# 07_-_PCIE_MINI.net
KiCad netlist of a schematic drawn in Altium Designer
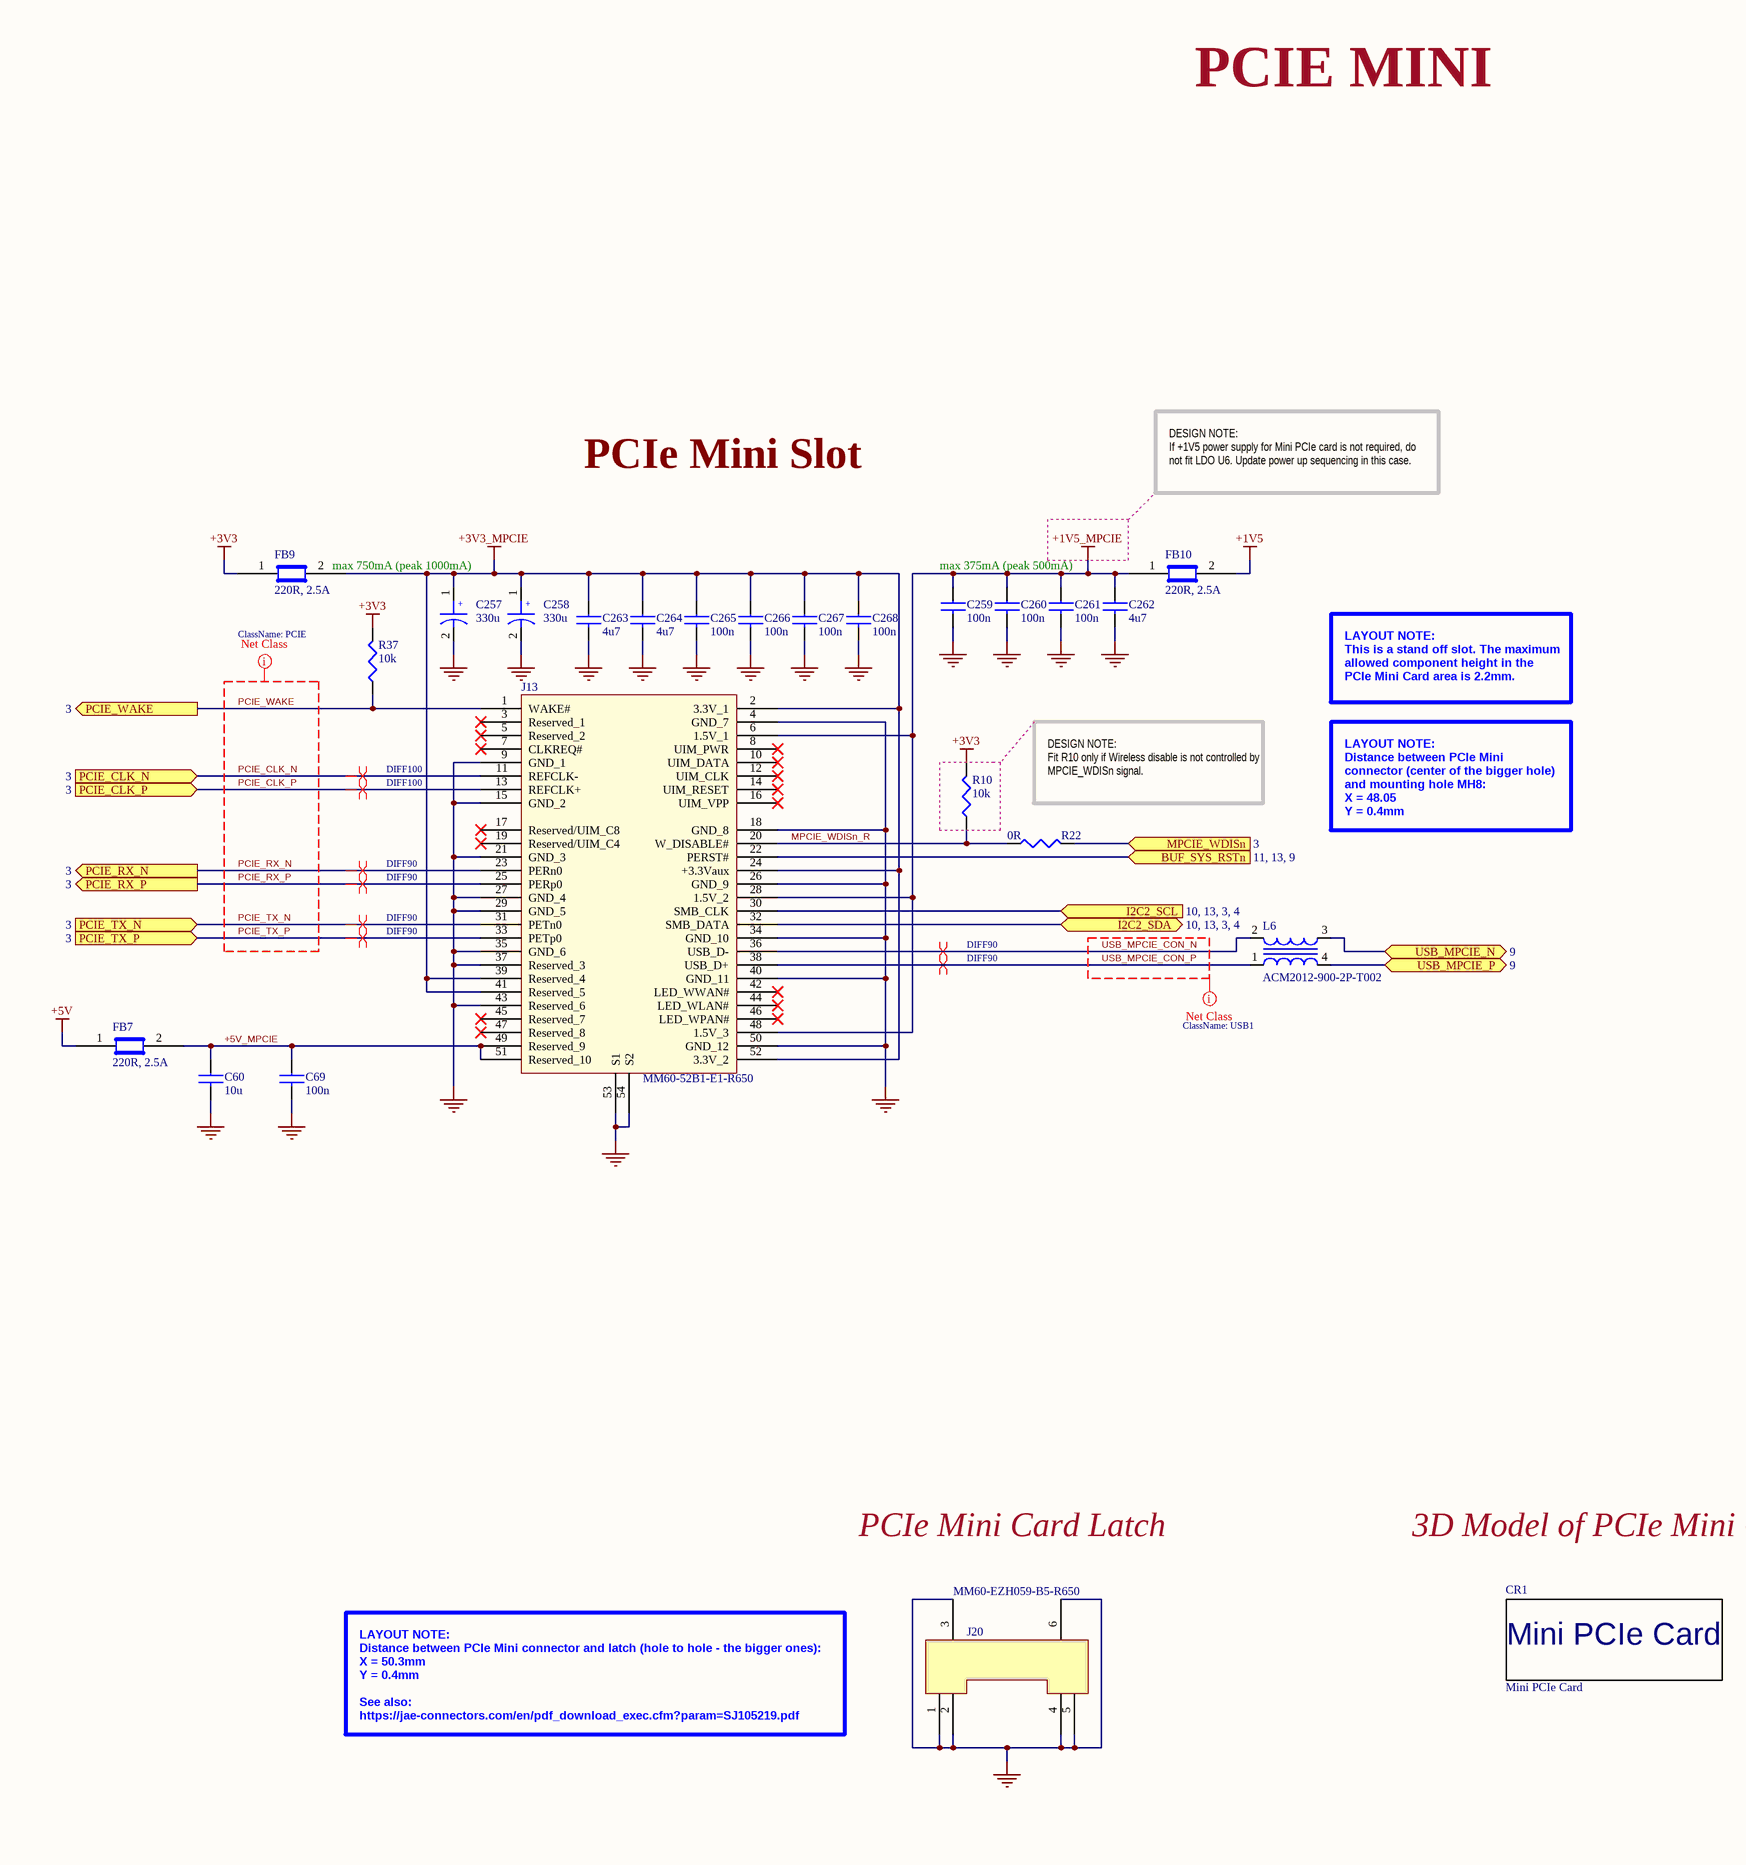
[diagram p0: [07] - PCIE MINI.SchDoc, left]
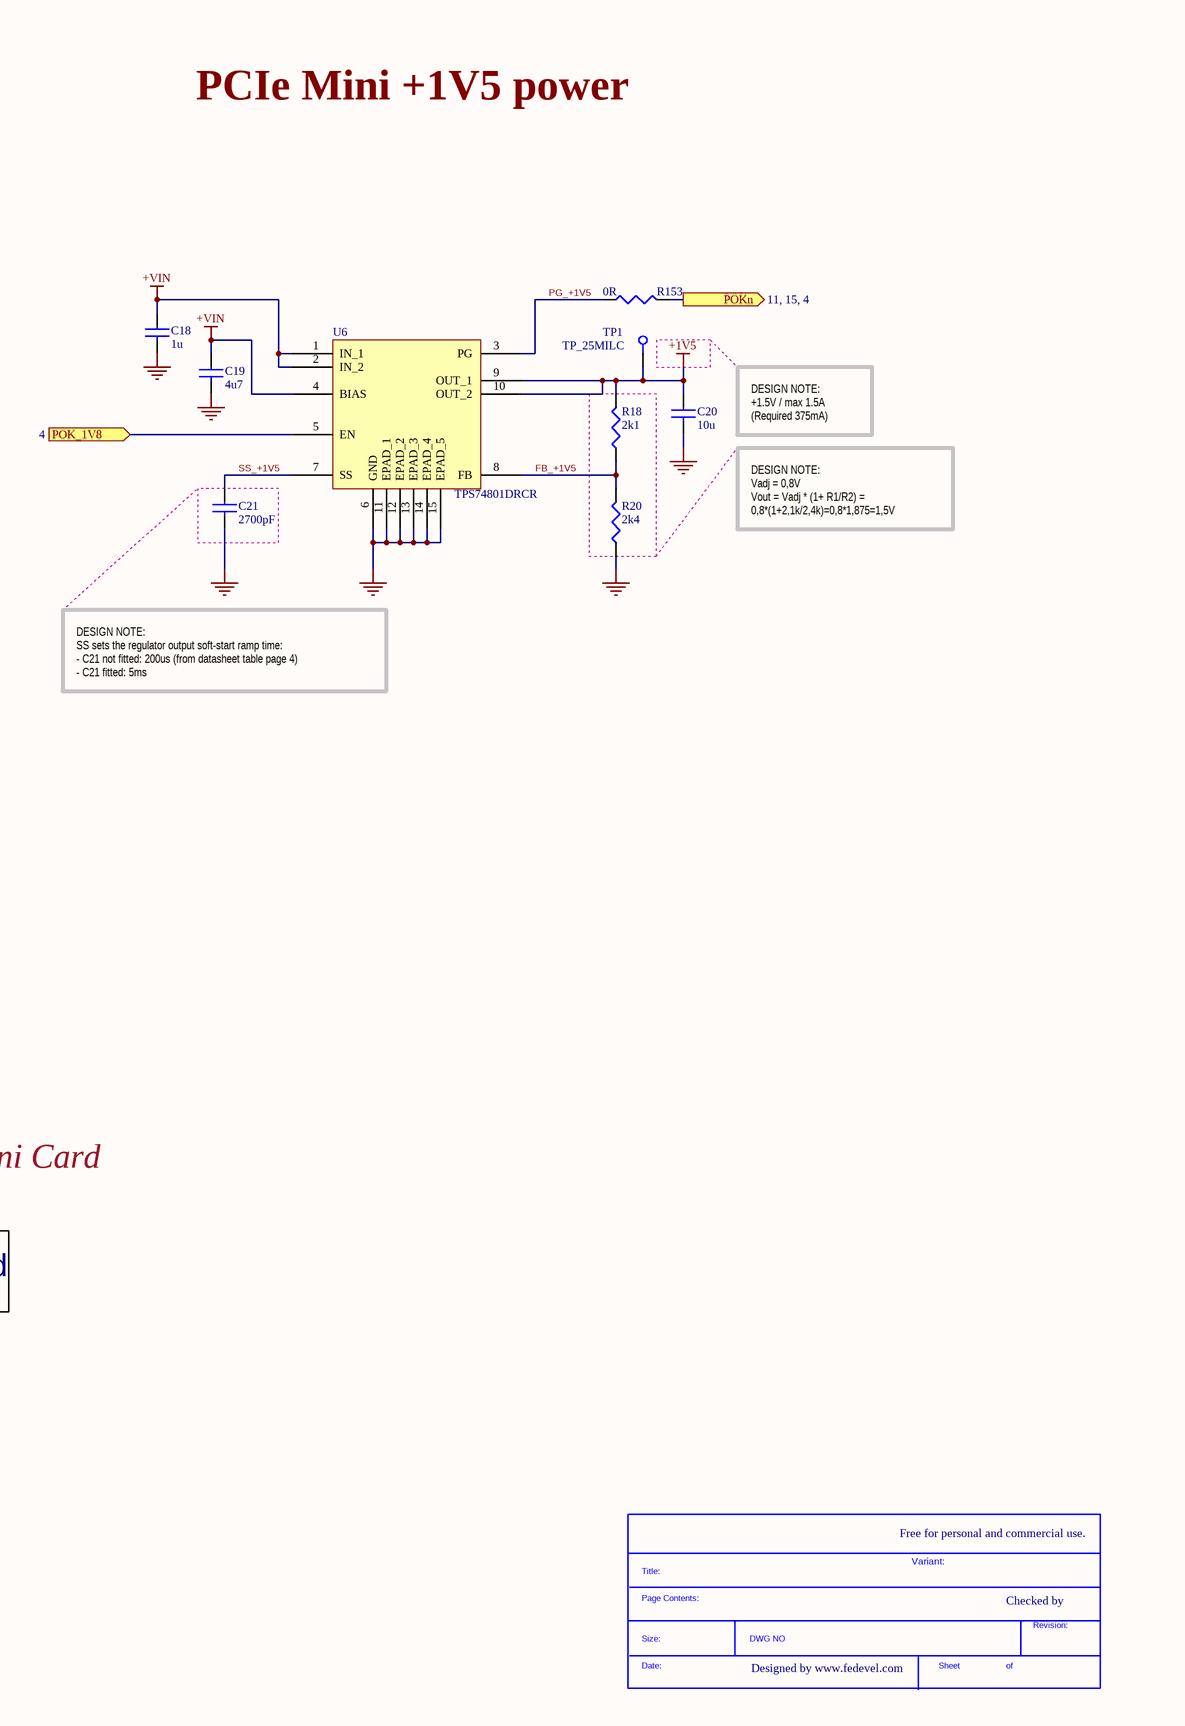
[diagram p1: [07] - PCIE MINI.SchDoc, right]

(export (version "E")
  (design (tool "Eeschema 10.0.6"))
  (components
    (comp (ref "C18")
      (value "1u")
      (footprint "C0402")
      (description "CAP CER 1.0UF 16V X5R 0402")
      (fields
        (field (name "MANUFACTURER") "TDK Corporation")
        (field (name "MANUFACTURER PART NUMBER") "C1005X5R1C105K")
      )
      (libsource (lib "Integrated_Library_FEDEVEL_APR_2015") (part "C1005X5R1C105K"))
    )
    (comp (ref "C19")
      (value "4u7")
      (footprint "C0402")
      (description "CAP CER 4.7UF 10V 20% X5R 0402")
      (fields
        (field (name "MANUFACTURER") "TDK Corporation")
        (field (name "MANUFACTURER PART NUMBER") "C1005X5R1A475M")
      )
      (libsource (lib "Integrated_Library_FEDEVEL_APR_2015") (part "C1005X5R1A475M"))
    )
    (comp (ref "C20")
      (value "10u")
      (footprint "C0603")
      (description "CAP CER 10UF 6.3V X5R 20% 0603")
      (fields
        (field (name "MANUFACTURER") "TDK Corporation")
        (field (name "MANUFACTURER PART NUMBER") "C1608X5R0J106M")
      )
      (libsource (lib "Integrated_Library_FEDEVEL_APR_2015") (part "C1608X5R0J106M"))
    )
    (comp (ref "C21")
      (value "2700pF")
      (footprint "C0402")
      (description "CAP CER 2700PF 50V 10% X7R 0402")
      (fields
        (field (name "MANUFACTURER") "Murata Electronics North America")
        (field (name "MANUFACTURER PART NUMBER") "GRM155R71H272KA01D")
      )
      (libsource (lib "Integrated_Library_FEDEVEL_APR_2015") (part "GRM155R71H272KA01D"))
    )
    (comp (ref "C60")
      (value "10u")
      (footprint "C0603")
      (description "CAP CER 10UF 6.3V X5R 20% 0603")
      (fields
        (field (name "MANUFACTURER") "TDK Corporation")
        (field (name "MANUFACTURER PART NUMBER") "C1608X5R0J106M")
      )
      (libsource (lib "Integrated_Library_FEDEVEL_APR_2015") (part "C1608X5R0J106M"))
    )
    (comp (ref "C69")
      (value "100n")
      (footprint "C0402")
      (description "CAP CER .10UF 50V X5R 10% 0402")
      (fields
        (field (name "MANUFACTURER") "TDK Corporation")
        (field (name "MANUFACTURER PART NUMBER") "C1005X5R1H104K")
      )
      (libsource (lib "Integrated_Library_FEDEVEL_APR_2015") (part "C1005X5R1H104K"))
    )
    (comp (ref "C257")
      (value "330u")
      (footprint "C2917")
      (description "CAP TANT 330UF 6.3V 20% 2917")
      (fields
        (field (name "MANUFACTURER") "Kemet")
        (field (name "MANUFACTURER PART NUMBER") "T520D337M006ATE045")
        (field (name ".CREATOR") "MM")
      )
      (libsource (lib "Integrated_Library_FEDEVEL_APR_2015") (part "T520D337M006ATE045"))
    )
    (comp (ref "C258")
      (value "330u")
      (footprint "C2917")
      (description "CAP TANT 330UF 6.3V 20% 2917")
      (fields
        (field (name "MANUFACTURER") "Kemet")
        (field (name "MANUFACTURER PART NUMBER") "T520D337M006ATE045")
        (field (name ".CREATOR") "MM")
      )
      (libsource (lib "Integrated_Library_FEDEVEL_APR_2015") (part "T520D337M006ATE045"))
    )
    (comp (ref "C259")
      (value "100n")
      (footprint "C0402")
      (description "CAP CER .10UF 50V X5R 10% 0402")
      (fields
        (field (name "MANUFACTURER") "TDK Corporation")
        (field (name "MANUFACTURER PART NUMBER") "C1005X5R1H104K")
      )
      (libsource (lib "Integrated_Library_FEDEVEL_APR_2015") (part "C1005X5R1H104K"))
    )
    (comp (ref "C260")
      (value "100n")
      (footprint "C0402")
      (description "CAP CER .10UF 50V X5R 10% 0402")
      (fields
        (field (name "MANUFACTURER") "TDK Corporation")
        (field (name "MANUFACTURER PART NUMBER") "C1005X5R1H104K")
      )
      (libsource (lib "Integrated_Library_FEDEVEL_APR_2015") (part "C1005X5R1H104K"))
    )
    (comp (ref "C261")
      (value "100n")
      (footprint "C0402")
      (description "CAP CER .10UF 50V X5R 10% 0402")
      (fields
        (field (name "MANUFACTURER") "TDK Corporation")
        (field (name "MANUFACTURER PART NUMBER") "C1005X5R1H104K")
      )
      (libsource (lib "Integrated_Library_FEDEVEL_APR_2015") (part "C1005X5R1H104K"))
    )
    (comp (ref "C262")
      (value "4u7")
      (footprint "C0402")
      (description "CAP CER 4.7UF 10V 20% X5R 0402")
      (fields
        (field (name "MANUFACTURER") "TDK Corporation")
        (field (name "MANUFACTURER PART NUMBER") "C1005X5R1A475M")
      )
      (libsource (lib "Integrated_Library_FEDEVEL_APR_2015") (part "C1005X5R1A475M"))
    )
    (comp (ref "C263")
      (value "4u7")
      (footprint "C0402")
      (description "CAP CER 4.7UF 10V 20% X5R 0402")
      (fields
        (field (name "MANUFACTURER") "TDK Corporation")
        (field (name "MANUFACTURER PART NUMBER") "C1005X5R1A475M")
      )
      (libsource (lib "Integrated_Library_FEDEVEL_APR_2015") (part "C1005X5R1A475M"))
    )
    (comp (ref "C264")
      (value "4u7")
      (footprint "C0402")
      (description "CAP CER 4.7UF 10V 20% X5R 0402")
      (fields
        (field (name "MANUFACTURER") "TDK Corporation")
        (field (name "MANUFACTURER PART NUMBER") "C1005X5R1A475M")
      )
      (libsource (lib "Integrated_Library_FEDEVEL_APR_2015") (part "C1005X5R1A475M"))
    )
    (comp (ref "C265")
      (value "100n")
      (footprint "C0402")
      (description "CAP CER .10UF 50V X5R 10% 0402")
      (fields
        (field (name "MANUFACTURER") "TDK Corporation")
        (field (name "MANUFACTURER PART NUMBER") "C1005X5R1H104K")
      )
      (libsource (lib "Integrated_Library_FEDEVEL_APR_2015") (part "C1005X5R1H104K"))
    )
    (comp (ref "C266")
      (value "100n")
      (footprint "C0402")
      (description "CAP CER .10UF 50V X5R 10% 0402")
      (fields
        (field (name "MANUFACTURER") "TDK Corporation")
        (field (name "MANUFACTURER PART NUMBER") "C1005X5R1H104K")
      )
      (libsource (lib "Integrated_Library_FEDEVEL_APR_2015") (part "C1005X5R1H104K"))
    )
    (comp (ref "C267")
      (value "100n")
      (footprint "C0402")
      (description "CAP CER .10UF 50V X5R 10% 0402")
      (fields
        (field (name "MANUFACTURER") "TDK Corporation")
        (field (name "MANUFACTURER PART NUMBER") "C1005X5R1H104K")
      )
      (libsource (lib "Integrated_Library_FEDEVEL_APR_2015") (part "C1005X5R1H104K"))
    )
    (comp (ref "C268")
      (value "100n")
      (footprint "C0402")
      (description "CAP CER .10UF 50V X5R 10% 0402")
      (fields
        (field (name "MANUFACTURER") "TDK Corporation")
        (field (name "MANUFACTURER PART NUMBER") "C1005X5R1H104K")
      )
      (libsource (lib "Integrated_Library_FEDEVEL_APR_2015") (part "C1005X5R1H104K"))
    )
    (comp (ref "CR1")
      (value "Mini PCIe Card")
      (footprint "Mini_PCIe_full card")
      (description "Card MIni PCIe")
      (fields (field (name ".CREATOR") "MM"))
      (libsource (lib "Integrated_Library_FEDEVEL_APR_2015") (part "Card_Mini_PCIe"))
    )
    (comp (ref "FB7")
      (value "220R, 2.5A")
      (footprint "C0603")
      (description "FERRITE CHIP 220 OHM 2500MA 0603")
      (fields
        (field (name "MANUFACTURER") "Murata Electronics North America")
        (field (name "MANUFACTURER PART NUMBER") "BLM18SG221TN1D")
      )
      (libsource (lib "Integrated_Library_FEDEVEL_APR_2015") (part "BLM18SG221TN1D"))
    )
    (comp (ref "FB9")
      (value "220R, 2.5A")
      (footprint "C0603")
      (description "FERRITE CHIP 220 OHM 2500MA 0603")
      (fields
        (field (name "MANUFACTURER") "Murata Electronics North America")
        (field (name "MANUFACTURER PART NUMBER") "BLM18SG221TN1D")
      )
      (libsource (lib "Integrated_Library_FEDEVEL_APR_2015") (part "BLM18SG221TN1D"))
    )
    (comp (ref "FB10")
      (value "220R, 2.5A")
      (footprint "C0603")
      (description "FERRITE CHIP 220 OHM 2500MA 0603")
      (fields
        (field (name "MANUFACTURER") "Murata Electronics North America")
        (field (name "MANUFACTURER PART NUMBER") "BLM18SG221TN1D")
      )
      (libsource (lib "Integrated_Library_FEDEVEL_APR_2015") (part "BLM18SG221TN1D"))
    )
    (comp (ref "J13")
      (value "MM60-52B1-E1-R650")
      (footprint "MINI_PCIE_52PIN_CARD_CON")
      (description "CONN MINI EXPRESS CARD 52POS SMD")
      (fields (field (name "MANUFACTURER") "JAE Electronics") (field (name ".CREATOR") "MM"))
      (libsource (lib "Integrated_Library_FEDEVEL_APR_2015") (part "MM60-52B1-E1-R650"))
    )
    (comp (ref "J20")
      (value "MM60-EZH059-B5-R650")
      (footprint "MINI_PCIE_52PIN_CARD_LATCH")
      (description "CONN MINI EXPRESS CARD LATCH SMD")
      (fields (field (name "MANUFACTURER") "JAE Electronics") (field (name ".CREATOR") "MM"))
      (libsource (lib "Integrated_Library_FEDEVEL_APR_2015") (part "MM60-EZH059-B5-R650"))
    )
    (comp (ref "L6")
      (value "ACM2012-900-2P-T002")
      (footprint "ACM2012")
      (description "CHOKE COMM MODE 90 OHM .4A SMD")
      (fields (field (name "MANUFACTURER") "TDK Corporation") (field (name "TOLERANCE") "±1%"))
      (libsource (lib "Integrated_Library_FEDEVEL_APR_2015") (part "ACM2012-900-2P-T002"))
    )
    (comp (ref "R10")
      (value "10k")
      (footprint "R0402")
      (description "RES 10.0K OHM 1/16W 1% 0402 SMD")
      (fields
        (field (name "MANUFACTURER") "Yageo")
        (field (name "MANUFACTURER PART NUMBER") "RC0402FR-0710KL")
      )
      (libsource (lib "Integrated_Library_FEDEVEL_APR_2015") (part "RC0402FR-0710KL"))
    )
    (comp (ref "R18")
      (value "2k1")
      (footprint "R0402")
      (description "RES 2.10K OHM 1/16W 1% 0402 SMD")
      (fields
        (field (name "MANUFACTURER") "Vishay Dale")
        (field (name "MANUFACTURER PART NUMBER") "CRCW04022K10FKED")
        (field (name ".CREATOR") "MM")
      )
      (libsource (lib "Integrated_Library_FEDEVEL_APR_2015") (part "CRCW04022K10FKED"))
    )
    (comp (ref "R20")
      (value "2k4")
      (footprint "R0402")
      (description "RES 2.40K OHM 1/16W 1% 0402 SMD")
      (fields
        (field (name "MANUFACTURER") "Vishay Dale")
        (field (name "MANUFACTURER PART NUMBER") "CRCW04022K40FKED")
      )
      (libsource (lib "Integrated_Library_FEDEVEL_APR_2015") (part "CRCW04022K40FKED"))
    )
    (comp (ref "R22")
      (value "0R")
      (footprint "R0402")
      (description "RES 0.0 OHM 1/16W 0402 SMD")
      (fields
        (field (name "MANUFACTURER") "Yageo")
        (field (name "MANUFACTURER PART NUMBER") "RC0402JR-070RL")
      )
      (libsource (lib "Integrated_Library_FEDEVEL_APR_2015") (part "RC0402JR-070RL"))
    )
    (comp (ref "R37")
      (value "10k")
      (footprint "R0402")
      (description "RES 10.0K OHM 1/16W 1% 0402 SMD")
      (fields
        (field (name "MANUFACTURER") "Yageo")
        (field (name "MANUFACTURER PART NUMBER") "RC0402FR-0710KL")
      )
      (libsource (lib "Integrated_Library_FEDEVEL_APR_2015") (part "RC0402FR-0710KL"))
    )
    (comp (ref "R153")
      (value "0R")
      (footprint "R0402")
      (description "RES 0.0 OHM 1/16W 0402 SMD")
      (fields
        (field (name "MANUFACTURER") "Yageo")
        (field (name "MANUFACTURER PART NUMBER") "RC0402JR-070RL")
      )
      (libsource (lib "Integrated_Library_FEDEVEL_APR_2015") (part "RC0402JR-070RL"))
    )
    (comp (ref "TP1")
      (value "TP_25MILC")
      (footprint "TP_25C")
      (description "Test Point 25mil")
      (libsource (lib "Integrated_Library_FEDEVEL_APR_2015") (part "TP_25MILC"))
    )
    (comp (ref "U6")
      (value "TPS74801DRCR")
      (footprint "DRC (S-PVSON-N10)")
      (description "IC REG LDO ADJ 1.5A 10SON")
      (fields (field (name "MANUFACTURER") "Texas Instruments") (field (name ".CREATOR") "MM"))
      (libsource (lib "Integrated_Library_FEDEVEL_APR_2015") (part "TPS74801DRCR"))
    )
  )
  (nets
    (net (code "1") (name "+1V5") (class "Default")
      (node (ref "C20") (pin "1") (pinfunction "1_1") (pintype "passive"))
      (node (ref "FB10") (pin "2") (pinfunction "2_2") (pintype "passive"))
      (node (ref "R18") (pin "2") (pinfunction "2_2") (pintype "passive"))
      (node (ref "TP1") (pin "1") (pinfunction "1_1") (pintype "passive"))
      (node (ref "U6") (pin "10") (pinfunction "OUT_2_10") (pintype "passive"))
      (node (ref "U6") (pin "9") (pinfunction "OUT_1_9") (pintype "passive"))
    )
    (net (code "2") (name "+1V5_MPCIE") (class "Default")
      (node (ref "C259") (pin "1") (pinfunction "1_1") (pintype "passive"))
      (node (ref "C260") (pin "1") (pinfunction "1_1") (pintype "passive"))
      (node (ref "C261") (pin "1") (pinfunction "1_1") (pintype "passive"))
      (node (ref "C262") (pin "1") (pinfunction "1_1") (pintype "passive"))
      (node (ref "FB10") (pin "1") (pinfunction "1_1") (pintype "passive"))
      (node (ref "J13") (pin "28") (pinfunction "1.5V_2_28") (pintype "passive"))
      (node (ref "J13") (pin "48") (pinfunction "1.5V_3_48") (pintype "passive"))
      (node (ref "J13") (pin "6") (pinfunction "1.5V_1_6") (pintype "passive"))
    )
    (net (code "3") (name "+3V3") (class "Default")
      (node (ref "FB9") (pin "1") (pinfunction "1_1") (pintype "passive"))
      (node (ref "R10") (pin "2") (pinfunction "2_2") (pintype "passive"))
      (node (ref "R37") (pin "2") (pinfunction "2_2") (pintype "passive"))
    )
    (net (code "4") (name "+3V3_MPCIE") (class "Default")
      (node (ref "C257") (pin "1") (pinfunction "1_1") (pintype "passive"))
      (node (ref "C258") (pin "1") (pinfunction "1_1") (pintype "passive"))
      (node (ref "C263") (pin "1") (pinfunction "1_1") (pintype "passive"))
      (node (ref "C264") (pin "1") (pinfunction "1_1") (pintype "passive"))
      (node (ref "C265") (pin "1") (pinfunction "1_1") (pintype "passive"))
      (node (ref "C266") (pin "1") (pinfunction "1_1") (pintype "passive"))
      (node (ref "C267") (pin "1") (pinfunction "1_1") (pintype "passive"))
      (node (ref "C268") (pin "1") (pinfunction "1_1") (pintype "passive"))
      (node (ref "FB9") (pin "2") (pinfunction "2_2") (pintype "passive"))
      (node (ref "J13") (pin "2") (pinfunction "3.3V_1_2") (pintype "passive"))
      (node (ref "J13") (pin "24") (pinfunction "+3.3Vaux_24") (pintype "passive"))
      (node (ref "J13") (pin "39") (pinfunction "Reserved_4_39") (pintype "passive"))
      (node (ref "J13") (pin "41") (pinfunction "Reserved_5_41") (pintype "passive"))
      (node (ref "J13") (pin "52") (pinfunction "3.3V_2_52") (pintype "passive"))
    )
    (net (code "5") (name "+5V") (class "Default")
      (node (ref "FB7") (pin "1") (pinfunction "1_1") (pintype "passive"))
    )
    (net (code "6") (name "+VIN") (class "Default")
      (node (ref "C18") (pin "1") (pinfunction "1_1") (pintype "passive"))
      (node (ref "C19") (pin "1") (pinfunction "1_1") (pintype "passive"))
      (node (ref "U6") (pin "1") (pinfunction "IN_1_1") (pintype "passive"))
      (node (ref "U6") (pin "2") (pinfunction "IN_2_2") (pintype "passive"))
      (node (ref "U6") (pin "4") (pinfunction "BIAS_4") (pintype "passive"))
    )
    (net (code "7") (name "/+5V_MPCIE") (class "Default")
      (node (ref "C60") (pin "1") (pinfunction "1_1") (pintype "passive"))
      (node (ref "C69") (pin "1") (pinfunction "1_1") (pintype "passive"))
      (node (ref "FB7") (pin "2") (pinfunction "2_2") (pintype "passive"))
      (node (ref "J13") (pin "49") (pinfunction "Reserved_9_49") (pintype "passive"))
      (node (ref "J13") (pin "51") (pinfunction "Reserved_10_51") (pintype "passive"))
    )
    (net (code "8") (name "/BUF_SYS_RSTn") (class "Default")
      (node (ref "J13") (pin "22") (pinfunction "PERST#_22") (pintype "passive"))
    )
    (net (code "9") (name "/FB_+1V5") (class "Default")
      (node (ref "R18") (pin "1") (pinfunction "1_1") (pintype "passive"))
      (node (ref "R20") (pin "2") (pinfunction "2_2") (pintype "passive"))
      (node (ref "U6") (pin "8") (pinfunction "FB_8") (pintype "passive"))
    )
    (net (code "10") (name "/I2C2_SCL") (class "Default")
      (node (ref "J13") (pin "30") (pinfunction "SMB_CLK_30") (pintype "passive"))
    )
    (net (code "11") (name "/I2C2_SDA") (class "Default")
      (node (ref "J13") (pin "32") (pinfunction "SMB_DATA_32") (pintype "passive"))
    )
    (net (code "12") (name "/MPCIE_WDISn") (class "Default")
      (node (ref "R22") (pin "2") (pinfunction "2_2") (pintype "passive"))
    )
    (net (code "13") (name "/MPCIE_WDISn_R") (class "Default")
      (node (ref "J13") (pin "20") (pinfunction "W_DISABLE#_20") (pintype "passive"))
      (node (ref "R10") (pin "1") (pinfunction "1_1") (pintype "passive"))
      (node (ref "R22") (pin "1") (pinfunction "1_1") (pintype "passive"))
    )
    (net (code "14") (name "/PCIE_CLK_N") (class "Default")
      (node (ref "J13") (pin "11") (pinfunction "REFCLK-_11") (pintype "passive"))
    )
    (net (code "15") (name "/PCIE_CLK_P") (class "Default")
      (node (ref "J13") (pin "13") (pinfunction "REFCLK+_13") (pintype "passive"))
    )
    (net (code "16") (name "/PCIE_RX_N") (class "Default")
      (node (ref "J13") (pin "23") (pinfunction "PERn0_23") (pintype "passive"))
    )
    (net (code "17") (name "/PCIE_RX_P") (class "Default")
      (node (ref "J13") (pin "25") (pinfunction "PERp0_25") (pintype "passive"))
    )
    (net (code "18") (name "/PCIE_TX_N") (class "Default")
      (node (ref "J13") (pin "31") (pinfunction "PETn0_31") (pintype "passive"))
    )
    (net (code "19") (name "/PCIE_TX_P") (class "Default")
      (node (ref "J13") (pin "33") (pinfunction "PETp0_33") (pintype "passive"))
    )
    (net (code "20") (name "/PCIE_WAKE") (class "Default")
      (node (ref "J13") (pin "1") (pinfunction "WAKE#_1") (pintype "passive"))
      (node (ref "R37") (pin "1") (pinfunction "1_1") (pintype "passive"))
    )
    (net (code "21") (name "/PG_+1V5") (class "Default")
      (node (ref "R153") (pin "1") (pinfunction "1_1") (pintype "passive"))
      (node (ref "U6") (pin "3") (pinfunction "PG_3") (pintype "passive"))
    )
    (net (code "22") (name "/POK_1V8") (class "Default")
      (node (ref "U6") (pin "5") (pinfunction "EN_5") (pintype "passive"))
    )
    (net (code "23") (name "/POKn") (class "Default")
      (node (ref "R153") (pin "2") (pinfunction "2_2") (pintype "passive"))
    )
    (net (code "24") (name "/SS_+1V5") (class "Default")
      (node (ref "C21") (pin "1") (pinfunction "1_1") (pintype "passive"))
      (node (ref "U6") (pin "7") (pinfunction "SS_7") (pintype "passive"))
    )
    (net (code "25") (name "/USB_MPCIE_CON_N") (class "Default")
      (node (ref "J13") (pin "36") (pinfunction "USB_D-_36") (pintype "passive"))
      (node (ref "L6") (pin "2") (pinfunction "2_2") (pintype "passive"))
    )
    (net (code "26") (name "/USB_MPCIE_CON_P") (class "Default")
      (node (ref "J13") (pin "38") (pinfunction "USB_D+_38") (pintype "passive"))
      (node (ref "L6") (pin "1") (pinfunction "1_1") (pintype "passive"))
    )
    (net (code "27") (name "/USB_MPCIE_N") (class "Default")
      (node (ref "L6") (pin "3") (pinfunction "3_3") (pintype "passive"))
    )
    (net (code "28") (name "/USB_MPCIE_P") (class "Default")
      (node (ref "L6") (pin "4") (pinfunction "4_4") (pintype "passive"))
    )
    (net (code "29") (name "GND") (class "Default")
      (node (ref "C18") (pin "2") (pinfunction "2_2") (pintype "passive"))
      (node (ref "C19") (pin "2") (pinfunction "2_2") (pintype "passive"))
      (node (ref "C20") (pin "2") (pinfunction "2_2") (pintype "passive"))
      (node (ref "C21") (pin "2") (pinfunction "2_2") (pintype "passive"))
      (node (ref "C257") (pin "2") (pinfunction "2_2") (pintype "passive"))
      (node (ref "C258") (pin "2") (pinfunction "2_2") (pintype "passive"))
      (node (ref "C259") (pin "2") (pinfunction "2_2") (pintype "passive"))
      (node (ref "C260") (pin "2") (pinfunction "2_2") (pintype "passive"))
      (node (ref "C261") (pin "2") (pinfunction "2_2") (pintype "passive"))
      (node (ref "C262") (pin "2") (pinfunction "2_2") (pintype "passive"))
      (node (ref "C263") (pin "2") (pinfunction "2_2") (pintype "passive"))
      (node (ref "C264") (pin "2") (pinfunction "2_2") (pintype "passive"))
      (node (ref "C265") (pin "2") (pinfunction "2_2") (pintype "passive"))
      (node (ref "C266") (pin "2") (pinfunction "2_2") (pintype "passive"))
      (node (ref "C267") (pin "2") (pinfunction "2_2") (pintype "passive"))
      (node (ref "C268") (pin "2") (pinfunction "2_2") (pintype "passive"))
      (node (ref "C60") (pin "2") (pinfunction "2_2") (pintype "passive"))
      (node (ref "C69") (pin "2") (pinfunction "2_2") (pintype "passive"))
      (node (ref "J13") (pin "15") (pinfunction "GND_2_15") (pintype "passive"))
      (node (ref "J13") (pin "18") (pinfunction "GND_8_18") (pintype "passive"))
      (node (ref "J13") (pin "21") (pinfunction "GND_3_21") (pintype "passive"))
      (node (ref "J13") (pin "26") (pinfunction "GND_9_26") (pintype "passive"))
      (node (ref "J13") (pin "27") (pinfunction "GND_4_27") (pintype "passive"))
      (node (ref "J13") (pin "29") (pinfunction "GND_5_29") (pintype "passive"))
      (node (ref "J13") (pin "34") (pinfunction "GND_10_34") (pintype "passive"))
      (node (ref "J13") (pin "35") (pinfunction "GND_6_35") (pintype "passive"))
      (node (ref "J13") (pin "37") (pinfunction "Reserved_3_37") (pintype "passive"))
      (node (ref "J13") (pin "4") (pinfunction "GND_7_4") (pintype "passive"))
      (node (ref "J13") (pin "40") (pinfunction "GND_11_40") (pintype "passive"))
      (node (ref "J13") (pin "43") (pinfunction "Reserved_6_43") (pintype "passive"))
      (node (ref "J13") (pin "50") (pinfunction "GND_12_50") (pintype "passive"))
      (node (ref "J13") (pin "53") (pinfunction "S1_53") (pintype "passive"))
      (node (ref "J13") (pin "54") (pinfunction "S2_54") (pintype "passive"))
      (node (ref "J13") (pin "9") (pinfunction "GND_1_9") (pintype "passive"))
      (node (ref "J20") (pin "1") (pinfunction "1_1") (pintype "passive"))
      (node (ref "J20") (pin "2") (pinfunction "2_2") (pintype "passive"))
      (node (ref "J20") (pin "3") (pinfunction "3_3") (pintype "passive"))
      (node (ref "J20") (pin "4") (pinfunction "4_4") (pintype "passive"))
      (node (ref "J20") (pin "5") (pinfunction "5_5") (pintype "passive"))
      (node (ref "J20") (pin "6") (pinfunction "6_6") (pintype "passive"))
      (node (ref "R20") (pin "1") (pinfunction "1_1") (pintype "passive"))
      (node (ref "U6") (pin "11") (pinfunction "EPAD_1_11") (pintype "passive"))
      (node (ref "U6") (pin "12") (pinfunction "EPAD_2_12") (pintype "passive"))
      (node (ref "U6") (pin "13") (pinfunction "EPAD_3_13") (pintype "passive"))
      (node (ref "U6") (pin "14") (pinfunction "EPAD_4_14") (pintype "passive"))
      (node (ref "U6") (pin "15") (pinfunction "EPAD_5_15") (pintype "passive"))
      (node (ref "U6") (pin "6") (pinfunction "GND_6") (pintype "passive"))
    )
    (net (code "30") (name "unconnected-(J13-CLKREQ#-Pad7)") (class "Default")
      (node (ref "J13") (pin "7") (pinfunction "CLKREQ#_7") (pintype "passive+no_connect"))
    )
    (net (code "31") (name "unconnected-(J13-LED_WLAN#-Pad44)") (class "Default")
      (node (ref "J13") (pin "44") (pinfunction "LED_WLAN#_44") (pintype "passive+no_connect"))
    )
    (net (code "32") (name "unconnected-(J13-LED_WPAN#-Pad46)") (class "Default")
      (node (ref "J13") (pin "46") (pinfunction "LED_WPAN#_46") (pintype "passive+no_connect"))
    )
    (net (code "33") (name "unconnected-(J13-LED_WWAN#-Pad42)") (class "Default")
      (node (ref "J13") (pin "42") (pinfunction "LED_WWAN#_42") (pintype "passive+no_connect"))
    )
    (net (code "34") (name "unconnected-(J13-Reserved_1-Pad3)") (class "Default")
      (node (ref "J13") (pin "3") (pinfunction "Reserved_1_3") (pintype "passive+no_connect"))
    )
    (net (code "35") (name "unconnected-(J13-Reserved_2-Pad5)") (class "Default")
      (node (ref "J13") (pin "5") (pinfunction "Reserved_2_5") (pintype "passive+no_connect"))
    )
    (net (code "36") (name "unconnected-(J13-Reserved_7-Pad45)") (class "Default")
      (node (ref "J13") (pin "45") (pinfunction "Reserved_7_45") (pintype "passive+no_connect"))
    )
    (net (code "37") (name "unconnected-(J13-Reserved_8-Pad47)") (class "Default")
      (node (ref "J13") (pin "47") (pinfunction "Reserved_8_47") (pintype "passive+no_connect"))
    )
    (net (code "38") (name "unconnected-(J13-Reserved{slash}UIM_C4-Pad19)") (class "Default")
      (node (ref "J13") (pin "19") (pinfunction "Reserved/UIM_C4_19") (pintype "passive+no_connect"))
    )
    (net (code "39") (name "unconnected-(J13-Reserved{slash}UIM_C8-Pad17)") (class "Default")
      (node (ref "J13") (pin "17") (pinfunction "Reserved/UIM_C8_17") (pintype "passive+no_connect"))
    )
    (net (code "40") (name "unconnected-(J13-UIM_CLK-Pad12)") (class "Default")
      (node (ref "J13") (pin "12") (pinfunction "UIM_CLK_12") (pintype "passive+no_connect"))
    )
    (net (code "41") (name "unconnected-(J13-UIM_DATA-Pad10)") (class "Default")
      (node (ref "J13") (pin "10") (pinfunction "UIM_DATA_10") (pintype "passive+no_connect"))
    )
    (net (code "42") (name "unconnected-(J13-UIM_PWR-Pad8)") (class "Default")
      (node (ref "J13") (pin "8") (pinfunction "UIM_PWR_8") (pintype "passive+no_connect"))
    )
    (net (code "43") (name "unconnected-(J13-UIM_RESET-Pad14)") (class "Default")
      (node (ref "J13") (pin "14") (pinfunction "UIM_RESET_14") (pintype "passive+no_connect"))
    )
    (net (code "44") (name "unconnected-(J13-UIM_VPP-Pad16)") (class "Default")
      (node (ref "J13") (pin "16") (pinfunction "UIM_VPP_16") (pintype "passive+no_connect"))
    )
  )
)
